# Logic_Outputs.net
KiCad netlist of a schematic drawn in Altium Designer
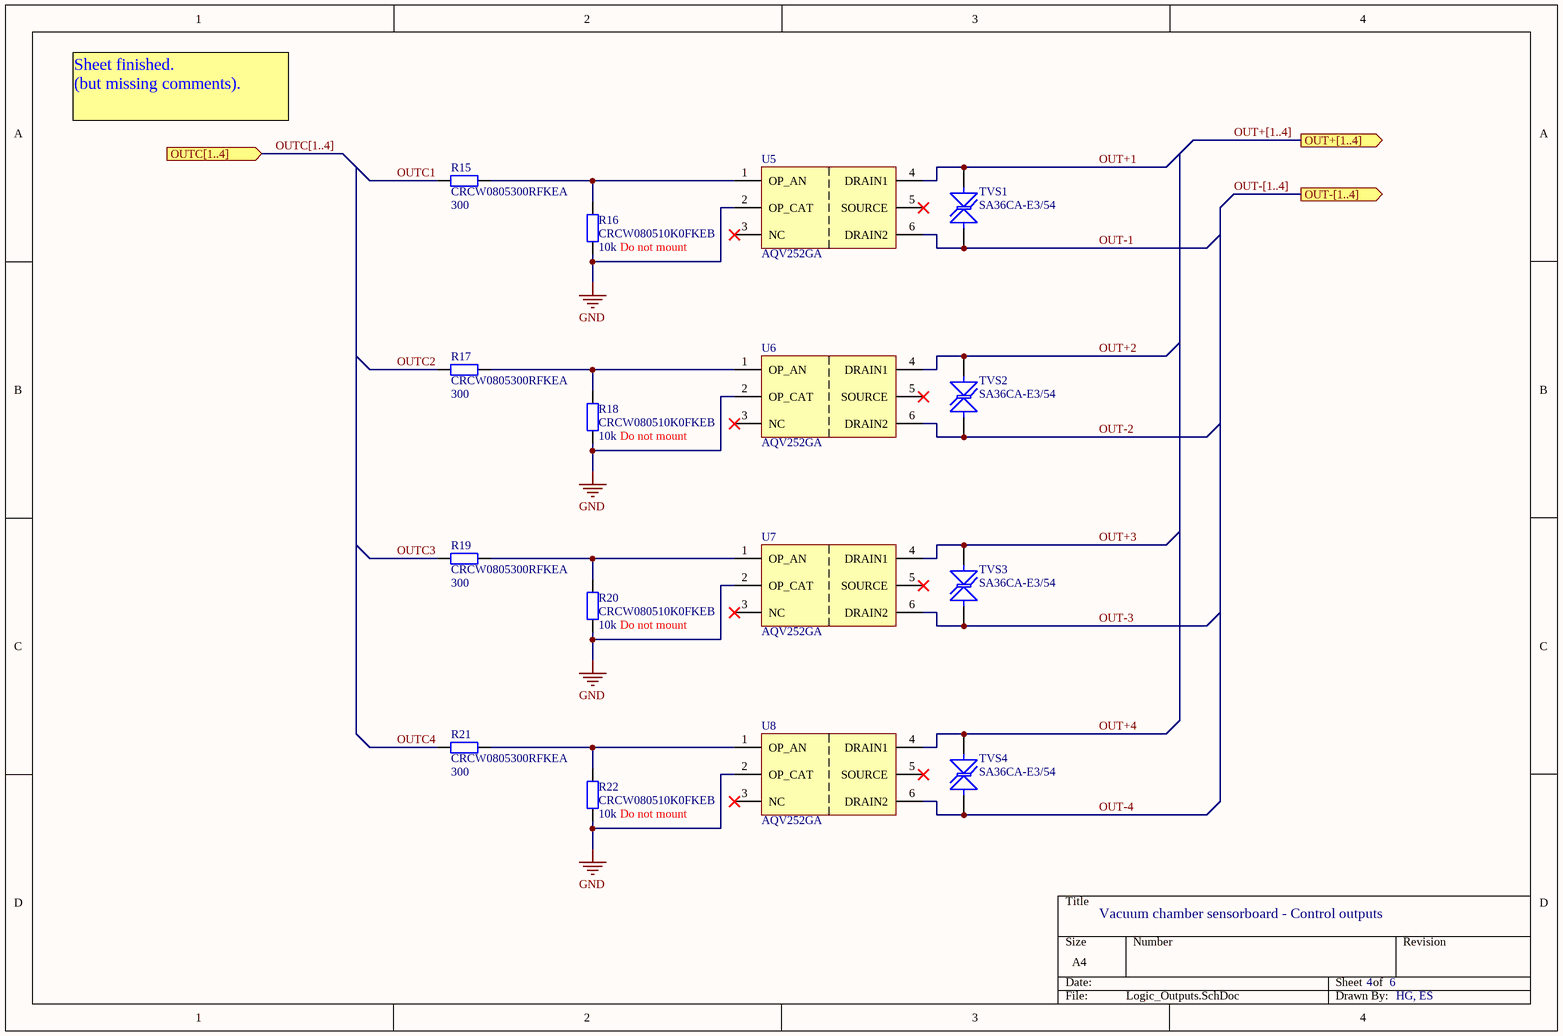
[diagram p0: Logic_Outputs.SchDoc]

(export (version "E")
  (design (tool "Eeschema 10.0.6"))
  (components
    (comp (ref "R15")
      (value "CRCW0805300RFKEA")
      (footprint "Res Vishay0805")
      (description "Thick film resistor, 1%, 125mW")
      (fields (field (name "MANUFACTURER") "Vishay") (field (name "ALTIUM_VALUE") "300"))
      (libsource (lib "EITlib") (part "CRCW0805300RFKEA"))
    )
    (comp (ref "R16")
      (value "CRCW080510K0FKEB")
      (footprint "Res Vishay0805")
      (description "Thick film resistor, 1%, 125mW")
      (fields (field (name "MANUFACTURER") "Vishay") (field (name "ALTIUM_VALUE") "10k"))
      (libsource (lib "EITlib") (part "CRCW080510K0FKEB"))
    )
    (comp (ref "R17")
      (value "CRCW0805300RFKEA")
      (footprint "Res Vishay0805")
      (description "Thick film resistor, 1%, 125mW")
      (fields (field (name "MANUFACTURER") "Vishay") (field (name "ALTIUM_VALUE") "300"))
      (libsource (lib "EITlib") (part "CRCW0805300RFKEA"))
    )
    (comp (ref "R18")
      (value "CRCW080510K0FKEB")
      (footprint "Res Vishay0805")
      (description "Thick film resistor, 1%, 125mW")
      (fields (field (name "MANUFACTURER") "Vishay") (field (name "ALTIUM_VALUE") "10k"))
      (libsource (lib "EITlib") (part "CRCW080510K0FKEB"))
    )
    (comp (ref "R19")
      (value "CRCW0805300RFKEA")
      (footprint "Res Vishay0805")
      (description "Thick film resistor, 1%, 125mW")
      (fields (field (name "MANUFACTURER") "Vishay") (field (name "ALTIUM_VALUE") "300"))
      (libsource (lib "EITlib") (part "CRCW0805300RFKEA"))
    )
    (comp (ref "R20")
      (value "CRCW080510K0FKEB")
      (footprint "Res Vishay0805")
      (description "Thick film resistor, 1%, 125mW")
      (fields (field (name "MANUFACTURER") "Vishay") (field (name "ALTIUM_VALUE") "10k"))
      (libsource (lib "EITlib") (part "CRCW080510K0FKEB"))
    )
    (comp (ref "R21")
      (value "CRCW0805300RFKEA")
      (footprint "Res Vishay0805")
      (description "Thick film resistor, 1%, 125mW")
      (fields (field (name "MANUFACTURER") "Vishay") (field (name "ALTIUM_VALUE") "300"))
      (libsource (lib "EITlib") (part "CRCW0805300RFKEA"))
    )
    (comp (ref "R22")
      (value "CRCW080510K0FKEB")
      (footprint "Res Vishay0805")
      (description "Thick film resistor, 1%, 125mW")
      (fields (field (name "MANUFACTURER") "Vishay") (field (name "ALTIUM_VALUE") "10k"))
      (libsource (lib "EITlib") (part "CRCW080510K0FKEB"))
    )
    (comp (ref "TVS1")
      (value "SA36CA-E3/54")
      (footprint "Diode Vishay")
      (description "TVS diode, bidirectional, 36 V")
      (fields (field (name "MANUFACTURER") "Vishay"))
      (libsource (lib "EITlib") (part "SA36CA-E3/54"))
    )
    (comp (ref "TVS2")
      (value "SA36CA-E3/54")
      (footprint "Diode Vishay")
      (description "TVS diode, bidirectional, 36 V")
      (fields (field (name "MANUFACTURER") "Vishay"))
      (libsource (lib "EITlib") (part "SA36CA-E3/54"))
    )
    (comp (ref "TVS3")
      (value "SA36CA-E3/54")
      (footprint "Diode Vishay")
      (description "TVS diode, bidirectional, 36 V")
      (fields (field (name "MANUFACTURER") "Vishay"))
      (libsource (lib "EITlib") (part "SA36CA-E3/54"))
    )
    (comp (ref "TVS4")
      (value "SA36CA-E3/54")
      (footprint "Diode Vishay")
      (description "TVS diode, bidirectional, 36 V")
      (fields (field (name "MANUFACTURER") "Vishay"))
      (libsource (lib "EITlib") (part "SA36CA-E3/54"))
    )
    (comp (ref "U5")
      (value "AQV252GA")
      (footprint "AQV252GA Panasonic")
      (description "Solid state relay, DC/AC, 60V, 2.5A")
      (fields (field (name "MANUFACTURER") "Panasonic"))
      (libsource (lib "EITlib") (part "AQV252GA"))
    )
    (comp (ref "U6")
      (value "AQV252GA")
      (footprint "AQV252GA Panasonic")
      (description "Solid state relay, DC/AC, 60V, 2.5A")
      (fields (field (name "MANUFACTURER") "Panasonic"))
      (libsource (lib "EITlib") (part "AQV252GA"))
    )
    (comp (ref "U7")
      (value "AQV252GA")
      (footprint "AQV252GA Panasonic")
      (description "Solid state relay, DC/AC, 60V, 2.5A")
      (fields (field (name "MANUFACTURER") "Panasonic"))
      (libsource (lib "EITlib") (part "AQV252GA"))
    )
    (comp (ref "U8")
      (value "AQV252GA")
      (footprint "AQV252GA Panasonic")
      (description "Solid state relay, DC/AC, 60V, 2.5A")
      (fields (field (name "MANUFACTURER") "Panasonic"))
      (libsource (lib "EITlib") (part "AQV252GA"))
    )
  )
  (nets
    (net (code "1") (name "/OUT+1") (class "Default")
      (node (ref "TVS1") (pin "2") (pinfunction "K_2") (pintype "passive"))
      (node (ref "U5") (pin "4") (pinfunction "DRAIN1_4") (pintype "passive"))
    )
    (net (code "2") (name "/OUT+2") (class "Default")
      (node (ref "TVS2") (pin "2") (pinfunction "K_2") (pintype "passive"))
      (node (ref "U6") (pin "4") (pinfunction "DRAIN1_4") (pintype "passive"))
    )
    (net (code "3") (name "/OUT+3") (class "Default")
      (node (ref "TVS3") (pin "2") (pinfunction "K_2") (pintype "passive"))
      (node (ref "U7") (pin "4") (pinfunction "DRAIN1_4") (pintype "passive"))
    )
    (net (code "4") (name "/OUT+4") (class "Default")
      (node (ref "TVS4") (pin "2") (pinfunction "K_2") (pintype "passive"))
      (node (ref "U8") (pin "4") (pinfunction "DRAIN1_4") (pintype "passive"))
    )
    (net (code "6") (name "/OUT-1") (class "Default")
      (node (ref "TVS1") (pin "1") (pinfunction "A_1") (pintype "passive"))
      (node (ref "U5") (pin "6") (pinfunction "DRAIN2_6") (pintype "passive"))
    )
    (net (code "7") (name "/OUT-2") (class "Default")
      (node (ref "TVS2") (pin "1") (pinfunction "A_1") (pintype "passive"))
      (node (ref "U6") (pin "6") (pinfunction "DRAIN2_6") (pintype "passive"))
    )
    (net (code "8") (name "/OUT-3") (class "Default")
      (node (ref "TVS3") (pin "1") (pinfunction "A_1") (pintype "passive"))
      (node (ref "U7") (pin "6") (pinfunction "DRAIN2_6") (pintype "passive"))
    )
    (net (code "9") (name "/OUT-4") (class "Default")
      (node (ref "TVS4") (pin "1") (pinfunction "A_1") (pintype "passive"))
      (node (ref "U8") (pin "6") (pinfunction "DRAIN2_6") (pintype "passive"))
    )
    (net (code "11") (name "/OUTC1") (class "Default")
      (node (ref "R15") (pin "1") (pinfunction "1_1") (pintype "passive"))
    )
    (net (code "12") (name "/OUTC2") (class "Default")
      (node (ref "R17") (pin "1") (pinfunction "1_1") (pintype "passive"))
    )
    (net (code "13") (name "/OUTC3") (class "Default")
      (node (ref "R19") (pin "1") (pinfunction "1_1") (pintype "passive"))
    )
    (net (code "14") (name "/OUTC4") (class "Default")
      (node (ref "R21") (pin "1") (pinfunction "1_1") (pintype "passive"))
    )
    (net (code "16") (name "GND") (class "Default")
      (node (ref "R16") (pin "1") (pinfunction "1_1") (pintype "passive"))
      (node (ref "R18") (pin "1") (pinfunction "1_1") (pintype "passive"))
      (node (ref "R20") (pin "1") (pinfunction "1_1") (pintype "passive"))
      (node (ref "R22") (pin "1") (pinfunction "1_1") (pintype "passive"))
      (node (ref "U5") (pin "2") (pinfunction "OP_CAT_2") (pintype "passive"))
      (node (ref "U6") (pin "2") (pinfunction "OP_CAT_2") (pintype "passive"))
      (node (ref "U7") (pin "2") (pinfunction "OP_CAT_2") (pintype "passive"))
      (node (ref "U8") (pin "2") (pinfunction "OP_CAT_2") (pintype "passive"))
    )
    (net (code "17") (name "Net-(U5-OP_AN)") (class "Default")
      (node (ref "R15") (pin "2") (pinfunction "2_2") (pintype "passive"))
      (node (ref "R16") (pin "2") (pinfunction "2_2") (pintype "passive"))
      (node (ref "U5") (pin "1") (pinfunction "OP_AN_1") (pintype "passive"))
    )
    (net (code "18") (name "Net-(U6-OP_AN)") (class "Default")
      (node (ref "R17") (pin "2") (pinfunction "2_2") (pintype "passive"))
      (node (ref "R18") (pin "2") (pinfunction "2_2") (pintype "passive"))
      (node (ref "U6") (pin "1") (pinfunction "OP_AN_1") (pintype "passive"))
    )
    (net (code "19") (name "Net-(U7-OP_AN)") (class "Default")
      (node (ref "R19") (pin "2") (pinfunction "2_2") (pintype "passive"))
      (node (ref "R20") (pin "2") (pinfunction "2_2") (pintype "passive"))
      (node (ref "U7") (pin "1") (pinfunction "OP_AN_1") (pintype "passive"))
    )
    (net (code "20") (name "Net-(U8-OP_AN)") (class "Default")
      (node (ref "R21") (pin "2") (pinfunction "2_2") (pintype "passive"))
      (node (ref "R22") (pin "2") (pinfunction "2_2") (pintype "passive"))
      (node (ref "U8") (pin "1") (pinfunction "OP_AN_1") (pintype "passive"))
    )
    (net (code "21") (name "unconnected-(U5-NC-Pad3)") (class "Default")
      (node (ref "U5") (pin "3") (pinfunction "NC_3") (pintype "passive+no_connect"))
    )
    (net (code "22") (name "unconnected-(U5-SOURCE-Pad5)") (class "Default")
      (node (ref "U5") (pin "5") (pinfunction "SOURCE_5") (pintype "passive+no_connect"))
    )
    (net (code "23") (name "unconnected-(U6-NC-Pad3)") (class "Default")
      (node (ref "U6") (pin "3") (pinfunction "NC_3") (pintype "passive+no_connect"))
    )
    (net (code "24") (name "unconnected-(U6-SOURCE-Pad5)") (class "Default")
      (node (ref "U6") (pin "5") (pinfunction "SOURCE_5") (pintype "passive+no_connect"))
    )
    (net (code "25") (name "unconnected-(U7-NC-Pad3)") (class "Default")
      (node (ref "U7") (pin "3") (pinfunction "NC_3") (pintype "passive+no_connect"))
    )
    (net (code "26") (name "unconnected-(U7-SOURCE-Pad5)") (class "Default")
      (node (ref "U7") (pin "5") (pinfunction "SOURCE_5") (pintype "passive+no_connect"))
    )
    (net (code "27") (name "unconnected-(U8-NC-Pad3)") (class "Default")
      (node (ref "U8") (pin "3") (pinfunction "NC_3") (pintype "passive+no_connect"))
    )
    (net (code "28") (name "unconnected-(U8-SOURCE-Pad5)") (class "Default")
      (node (ref "U8") (pin "5") (pinfunction "SOURCE_5") (pintype "passive+no_connect"))
    )
  )
)
